# modulo_sensores_routing_option1.net
KiCad netlist of a schematic drawn in EAGLE
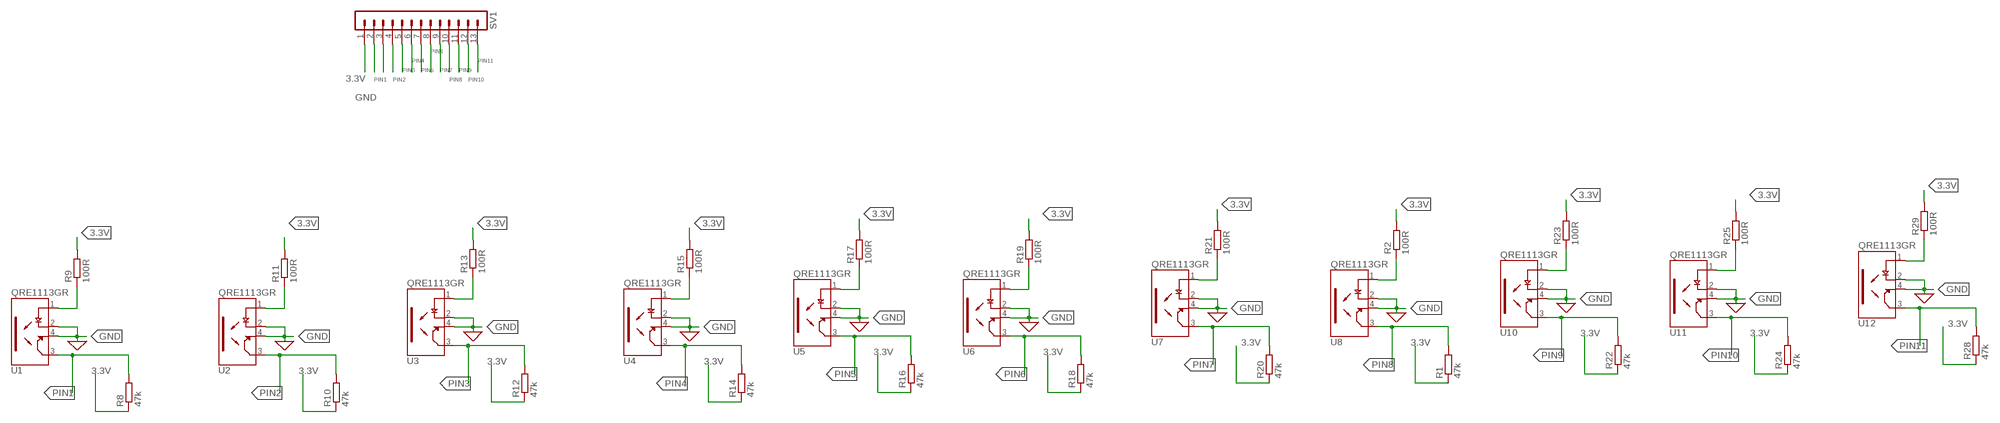
[diagram p0: schematic, sheet 1]

(export (version "E")
  (design (tool "Eeschema 10.0.6"))
  (components
    (comp (ref "R1")
      (value "47k")
      (footprint "eagle-import:M0805")
      (libsource (lib "eagle-import") (part "R-EU_M0805"))
    )
    (comp (ref "R2")
      (value "100R")
      (footprint "eagle-import:M0805")
      (libsource (lib "eagle-import") (part "R-EU_M0805"))
    )
    (comp (ref "R8")
      (value "47k")
      (footprint "eagle-import:M0805")
      (libsource (lib "eagle-import") (part "R-EU_M0805"))
    )
    (comp (ref "R9")
      (value "100R")
      (footprint "eagle-import:M0805")
      (libsource (lib "eagle-import") (part "R-EU_M0805"))
    )
    (comp (ref "R10")
      (value "47k")
      (footprint "eagle-import:M0805")
      (libsource (lib "eagle-import") (part "R-EU_M0805"))
    )
    (comp (ref "R11")
      (value "100R")
      (footprint "eagle-import:M0805")
      (libsource (lib "eagle-import") (part "R-EU_M0805"))
    )
    (comp (ref "R12")
      (value "47k")
      (footprint "eagle-import:M0805")
      (libsource (lib "eagle-import") (part "R-EU_M0805"))
    )
    (comp (ref "R13")
      (value "100R")
      (footprint "eagle-import:M0805")
      (libsource (lib "eagle-import") (part "R-EU_M0805"))
    )
    (comp (ref "R14")
      (value "47k")
      (footprint "eagle-import:M0805")
      (libsource (lib "eagle-import") (part "R-EU_M0805"))
    )
    (comp (ref "R15")
      (value "100R")
      (footprint "eagle-import:M0805")
      (libsource (lib "eagle-import") (part "R-EU_M0805"))
    )
    (comp (ref "R16")
      (value "47k")
      (footprint "eagle-import:M0805")
      (libsource (lib "eagle-import") (part "R-EU_M0805"))
    )
    (comp (ref "R17")
      (value "100R")
      (footprint "eagle-import:M0805")
      (libsource (lib "eagle-import") (part "R-EU_M0805"))
    )
    (comp (ref "R18")
      (value "47k")
      (footprint "eagle-import:M0805")
      (libsource (lib "eagle-import") (part "R-EU_M0805"))
    )
    (comp (ref "R19")
      (value "100R")
      (footprint "eagle-import:M0805")
      (libsource (lib "eagle-import") (part "R-EU_M0805"))
    )
    (comp (ref "R20")
      (value "47k")
      (footprint "eagle-import:M0805")
      (libsource (lib "eagle-import") (part "R-EU_M0805"))
    )
    (comp (ref "R21")
      (value "100R")
      (footprint "eagle-import:M0805")
      (libsource (lib "eagle-import") (part "R-EU_M0805"))
    )
    (comp (ref "R22")
      (value "47k")
      (footprint "eagle-import:M0805")
      (libsource (lib "eagle-import") (part "R-EU_M0805"))
    )
    (comp (ref "R23")
      (value "100R")
      (footprint "eagle-import:M0805")
      (libsource (lib "eagle-import") (part "R-EU_M0805"))
    )
    (comp (ref "R24")
      (value "47k")
      (footprint "eagle-import:M0805")
      (libsource (lib "eagle-import") (part "R-EU_M0805"))
    )
    (comp (ref "R25")
      (value "100R")
      (footprint "eagle-import:M0805")
      (libsource (lib "eagle-import") (part "R-EU_M0805"))
    )
    (comp (ref "R28")
      (value "47k")
      (footprint "eagle-import:M0805")
      (libsource (lib "eagle-import") (part "R-EU_M0805"))
    )
    (comp (ref "R29")
      (value "100R")
      (footprint "eagle-import:M0805")
      (libsource (lib "eagle-import") (part "R-EU_M0805"))
    )
    (comp (ref "SV1")
      (value "MA13-1")
      (footprint "eagle-import:MA13-1")
      (libsource (lib "eagle-import") (part "MA13-1"))
    )
    (comp (ref "U1")
      (value "QRE1113GR")
      (footprint "eagle-import:SOIC180P460X187-4N")
      (fields (field (name "MF") "ON Semiconductor"))
      (libsource (lib "eagle-import") (part "QRE1113GR"))
    )
    (comp (ref "U2")
      (value "QRE1113GR")
      (footprint "eagle-import:SOIC180P460X187-4N")
      (fields (field (name "MF") "ON Semiconductor"))
      (libsource (lib "eagle-import") (part "QRE1113GR"))
    )
    (comp (ref "U3")
      (value "QRE1113GR")
      (footprint "eagle-import:SOIC180P460X187-4N")
      (fields (field (name "MF") "ON Semiconductor"))
      (libsource (lib "eagle-import") (part "QRE1113GR"))
    )
    (comp (ref "U4")
      (value "QRE1113GR")
      (footprint "eagle-import:SOIC180P460X187-4N")
      (fields (field (name "MF") "ON Semiconductor"))
      (libsource (lib "eagle-import") (part "QRE1113GR"))
    )
    (comp (ref "U5")
      (value "QRE1113GR")
      (footprint "eagle-import:SOIC180P460X187-4N")
      (fields (field (name "MF") "ON Semiconductor"))
      (libsource (lib "eagle-import") (part "QRE1113GR"))
    )
    (comp (ref "U6")
      (value "QRE1113GR")
      (footprint "eagle-import:SOIC180P460X187-4N")
      (fields (field (name "MF") "ON Semiconductor"))
      (libsource (lib "eagle-import") (part "QRE1113GR"))
    )
    (comp (ref "U7")
      (value "QRE1113GR")
      (footprint "eagle-import:SOIC180P460X187-4N")
      (fields (field (name "MF") "ON Semiconductor"))
      (libsource (lib "eagle-import") (part "QRE1113GR"))
    )
    (comp (ref "U8")
      (value "QRE1113GR")
      (footprint "eagle-import:SOIC180P460X187-4N")
      (fields (field (name "MF") "ON Semiconductor"))
      (libsource (lib "eagle-import") (part "QRE1113GR"))
    )
    (comp (ref "U10")
      (value "QRE1113GR")
      (footprint "eagle-import:SOIC180P460X187-4N")
      (fields (field (name "MF") "ON Semiconductor"))
      (libsource (lib "eagle-import") (part "QRE1113GR"))
    )
    (comp (ref "U11")
      (value "QRE1113GR")
      (footprint "eagle-import:SOIC180P460X187-4N")
      (fields (field (name "MF") "ON Semiconductor"))
      (libsource (lib "eagle-import") (part "QRE1113GR"))
    )
    (comp (ref "U12")
      (value "QRE1113GR")
      (footprint "eagle-import:SOIC180P460X187-4N")
      (fields (field (name "MF") "ON Semiconductor"))
      (libsource (lib "eagle-import") (part "QRE1113GR"))
    )
  )
  (nets
    (net (code "1") (name "3.3V") (class "Default")
      (node (ref "R1") (pin "1") (pinfunction "1_1") (pintype "passive"))
      (node (ref "R10") (pin "1") (pinfunction "1_1") (pintype "passive"))
      (node (ref "R11") (pin "2") (pinfunction "2_2") (pintype "passive"))
      (node (ref "R12") (pin "1") (pinfunction "1_1") (pintype "passive"))
      (node (ref "R13") (pin "2") (pinfunction "2_2") (pintype "passive"))
      (node (ref "R14") (pin "1") (pinfunction "1_1") (pintype "passive"))
      (node (ref "R15") (pin "2") (pinfunction "2_2") (pintype "passive"))
      (node (ref "R16") (pin "1") (pinfunction "1_1") (pintype "passive"))
      (node (ref "R17") (pin "2") (pinfunction "2_2") (pintype "passive"))
      (node (ref "R18") (pin "1") (pinfunction "1_1") (pintype "passive"))
      (node (ref "R19") (pin "2") (pinfunction "2_2") (pintype "passive"))
      (node (ref "R2") (pin "2") (pinfunction "2_2") (pintype "passive"))
      (node (ref "R20") (pin "1") (pinfunction "1_1") (pintype "passive"))
      (node (ref "R21") (pin "2") (pinfunction "2_2") (pintype "passive"))
      (node (ref "R22") (pin "1") (pinfunction "1_1") (pintype "passive"))
      (node (ref "R23") (pin "2") (pinfunction "2_2") (pintype "passive"))
      (node (ref "R24") (pin "1") (pinfunction "1_1") (pintype "passive"))
      (node (ref "R25") (pin "2") (pinfunction "2_2") (pintype "passive"))
      (node (ref "R28") (pin "1") (pinfunction "1_1") (pintype "passive"))
      (node (ref "R29") (pin "2") (pinfunction "2_2") (pintype "passive"))
      (node (ref "R8") (pin "1") (pinfunction "1_1") (pintype "passive"))
      (node (ref "R9") (pin "2") (pinfunction "2_2") (pintype "passive"))
      (node (ref "SV1") (pin "1") (pinfunction "1_1") (pintype "passive"))
    )
    (net (code "2") (name "GND") (class "Default")
      (node (ref "SV1") (pin "2") (pinfunction "2_2") (pintype "passive"))
      (node (ref "U1") (pin "2") (pinfunction "C_2") (pintype "passive"))
      (node (ref "U1") (pin "4") (pinfunction "ET_4") (pintype "passive"))
      (node (ref "U10") (pin "2") (pinfunction "C_2") (pintype "passive"))
      (node (ref "U10") (pin "4") (pinfunction "ET_4") (pintype "passive"))
      (node (ref "U11") (pin "2") (pinfunction "C_2") (pintype "passive"))
      (node (ref "U11") (pin "4") (pinfunction "ET_4") (pintype "passive"))
      (node (ref "U12") (pin "2") (pinfunction "C_2") (pintype "passive"))
      (node (ref "U12") (pin "4") (pinfunction "ET_4") (pintype "passive"))
      (node (ref "U2") (pin "2") (pinfunction "C_2") (pintype "passive"))
      (node (ref "U2") (pin "4") (pinfunction "ET_4") (pintype "passive"))
      (node (ref "U3") (pin "2") (pinfunction "C_2") (pintype "passive"))
      (node (ref "U3") (pin "4") (pinfunction "ET_4") (pintype "passive"))
      (node (ref "U4") (pin "2") (pinfunction "C_2") (pintype "passive"))
      (node (ref "U4") (pin "4") (pinfunction "ET_4") (pintype "passive"))
      (node (ref "U5") (pin "2") (pinfunction "C_2") (pintype "passive"))
      (node (ref "U5") (pin "4") (pinfunction "ET_4") (pintype "passive"))
      (node (ref "U6") (pin "2") (pinfunction "C_2") (pintype "passive"))
      (node (ref "U6") (pin "4") (pinfunction "ET_4") (pintype "passive"))
      (node (ref "U7") (pin "2") (pinfunction "C_2") (pintype "passive"))
      (node (ref "U7") (pin "4") (pinfunction "ET_4") (pintype "passive"))
      (node (ref "U8") (pin "2") (pinfunction "C_2") (pintype "passive"))
      (node (ref "U8") (pin "4") (pinfunction "ET_4") (pintype "passive"))
    )
    (net (code "3") (name "Net-(U1-A)") (class "Default")
      (node (ref "R9") (pin "1") (pinfunction "1_1") (pintype "passive"))
      (node (ref "U1") (pin "1") (pinfunction "A_1") (pintype "passive"))
    )
    (net (code "4") (name "Net-(U2-A)") (class "Default")
      (node (ref "R11") (pin "1") (pinfunction "1_1") (pintype "passive"))
      (node (ref "U2") (pin "1") (pinfunction "A_1") (pintype "passive"))
    )
    (net (code "5") (name "Net-(U3-A)") (class "Default")
      (node (ref "R13") (pin "1") (pinfunction "1_1") (pintype "passive"))
      (node (ref "U3") (pin "1") (pinfunction "A_1") (pintype "passive"))
    )
    (net (code "6") (name "Net-(U4-A)") (class "Default")
      (node (ref "R15") (pin "1") (pinfunction "1_1") (pintype "passive"))
      (node (ref "U4") (pin "1") (pinfunction "A_1") (pintype "passive"))
    )
    (net (code "7") (name "Net-(U5-A)") (class "Default")
      (node (ref "R17") (pin "1") (pinfunction "1_1") (pintype "passive"))
      (node (ref "U5") (pin "1") (pinfunction "A_1") (pintype "passive"))
    )
    (net (code "8") (name "Net-(U6-A)") (class "Default")
      (node (ref "R19") (pin "1") (pinfunction "1_1") (pintype "passive"))
      (node (ref "U6") (pin "1") (pinfunction "A_1") (pintype "passive"))
    )
    (net (code "9") (name "Net-(U7-A)") (class "Default")
      (node (ref "R21") (pin "1") (pinfunction "1_1") (pintype "passive"))
      (node (ref "U7") (pin "1") (pinfunction "A_1") (pintype "passive"))
    )
    (net (code "10") (name "Net-(U8-A)") (class "Default")
      (node (ref "R2") (pin "1") (pinfunction "1_1") (pintype "passive"))
      (node (ref "U8") (pin "1") (pinfunction "A_1") (pintype "passive"))
    )
    (net (code "11") (name "Net-(U10-A)") (class "Default")
      (node (ref "R23") (pin "1") (pinfunction "1_1") (pintype "passive"))
      (node (ref "U10") (pin "1") (pinfunction "A_1") (pintype "passive"))
    )
    (net (code "12") (name "Net-(U11-A)") (class "Default")
      (node (ref "R25") (pin "1") (pinfunction "1_1") (pintype "passive"))
      (node (ref "U11") (pin "1") (pinfunction "A_1") (pintype "passive"))
    )
    (net (code "13") (name "Net-(U12-A)") (class "Default")
      (node (ref "R29") (pin "1") (pinfunction "1_1") (pintype "passive"))
      (node (ref "U12") (pin "1") (pinfunction "A_1") (pintype "passive"))
    )
    (net (code "14") (name "PIN1") (class "Default")
      (node (ref "R8") (pin "2") (pinfunction "2_2") (pintype "passive"))
      (node (ref "SV1") (pin "3") (pinfunction "3_3") (pintype "passive"))
      (node (ref "U1") (pin "3") (pinfunction "CT_3") (pintype "passive"))
    )
    (net (code "15") (name "PIN2") (class "Default")
      (node (ref "R10") (pin "2") (pinfunction "2_2") (pintype "passive"))
      (node (ref "SV1") (pin "4") (pinfunction "4_4") (pintype "passive"))
      (node (ref "U2") (pin "3") (pinfunction "CT_3") (pintype "passive"))
    )
    (net (code "16") (name "PIN3") (class "Default")
      (node (ref "R12") (pin "2") (pinfunction "2_2") (pintype "passive"))
      (node (ref "SV1") (pin "5") (pinfunction "5_5") (pintype "passive"))
      (node (ref "U3") (pin "3") (pinfunction "CT_3") (pintype "passive"))
    )
    (net (code "17") (name "PIN4") (class "Default")
      (node (ref "R14") (pin "2") (pinfunction "2_2") (pintype "passive"))
      (node (ref "SV1") (pin "6") (pinfunction "6_6") (pintype "passive"))
      (node (ref "U4") (pin "3") (pinfunction "CT_3") (pintype "passive"))
    )
    (net (code "18") (name "PIN5") (class "Default")
      (node (ref "R16") (pin "2") (pinfunction "2_2") (pintype "passive"))
      (node (ref "SV1") (pin "7") (pinfunction "7_7") (pintype "passive"))
      (node (ref "U5") (pin "3") (pinfunction "CT_3") (pintype "passive"))
    )
    (net (code "19") (name "PIN6") (class "Default")
      (node (ref "R18") (pin "2") (pinfunction "2_2") (pintype "passive"))
      (node (ref "SV1") (pin "8") (pinfunction "8_8") (pintype "passive"))
      (node (ref "U6") (pin "3") (pinfunction "CT_3") (pintype "passive"))
    )
    (net (code "20") (name "PIN7") (class "Default")
      (node (ref "R20") (pin "2") (pinfunction "2_2") (pintype "passive"))
      (node (ref "SV1") (pin "9") (pinfunction "9_9") (pintype "passive"))
      (node (ref "U7") (pin "3") (pinfunction "CT_3") (pintype "passive"))
    )
    (net (code "21") (name "PIN8") (class "Default")
      (node (ref "R1") (pin "2") (pinfunction "2_2") (pintype "passive"))
      (node (ref "SV1") (pin "10") (pinfunction "10_10") (pintype "passive"))
      (node (ref "U8") (pin "3") (pinfunction "CT_3") (pintype "passive"))
    )
    (net (code "22") (name "PIN9") (class "Default")
      (node (ref "R22") (pin "2") (pinfunction "2_2") (pintype "passive"))
      (node (ref "SV1") (pin "11") (pinfunction "11_11") (pintype "passive"))
      (node (ref "U10") (pin "3") (pinfunction "CT_3") (pintype "passive"))
    )
    (net (code "23") (name "PIN10") (class "Default")
      (node (ref "R24") (pin "2") (pinfunction "2_2") (pintype "passive"))
      (node (ref "SV1") (pin "12") (pinfunction "12_12") (pintype "passive"))
      (node (ref "U11") (pin "3") (pinfunction "CT_3") (pintype "passive"))
    )
    (net (code "24") (name "PIN11") (class "Default")
      (node (ref "R28") (pin "2") (pinfunction "2_2") (pintype "passive"))
      (node (ref "SV1") (pin "13") (pinfunction "13_13") (pintype "passive"))
      (node (ref "U12") (pin "3") (pinfunction "CT_3") (pintype "passive"))
    )
  )
)
